# schematicsch.net
KiCad netlist of a schematic drawn in EAGLE
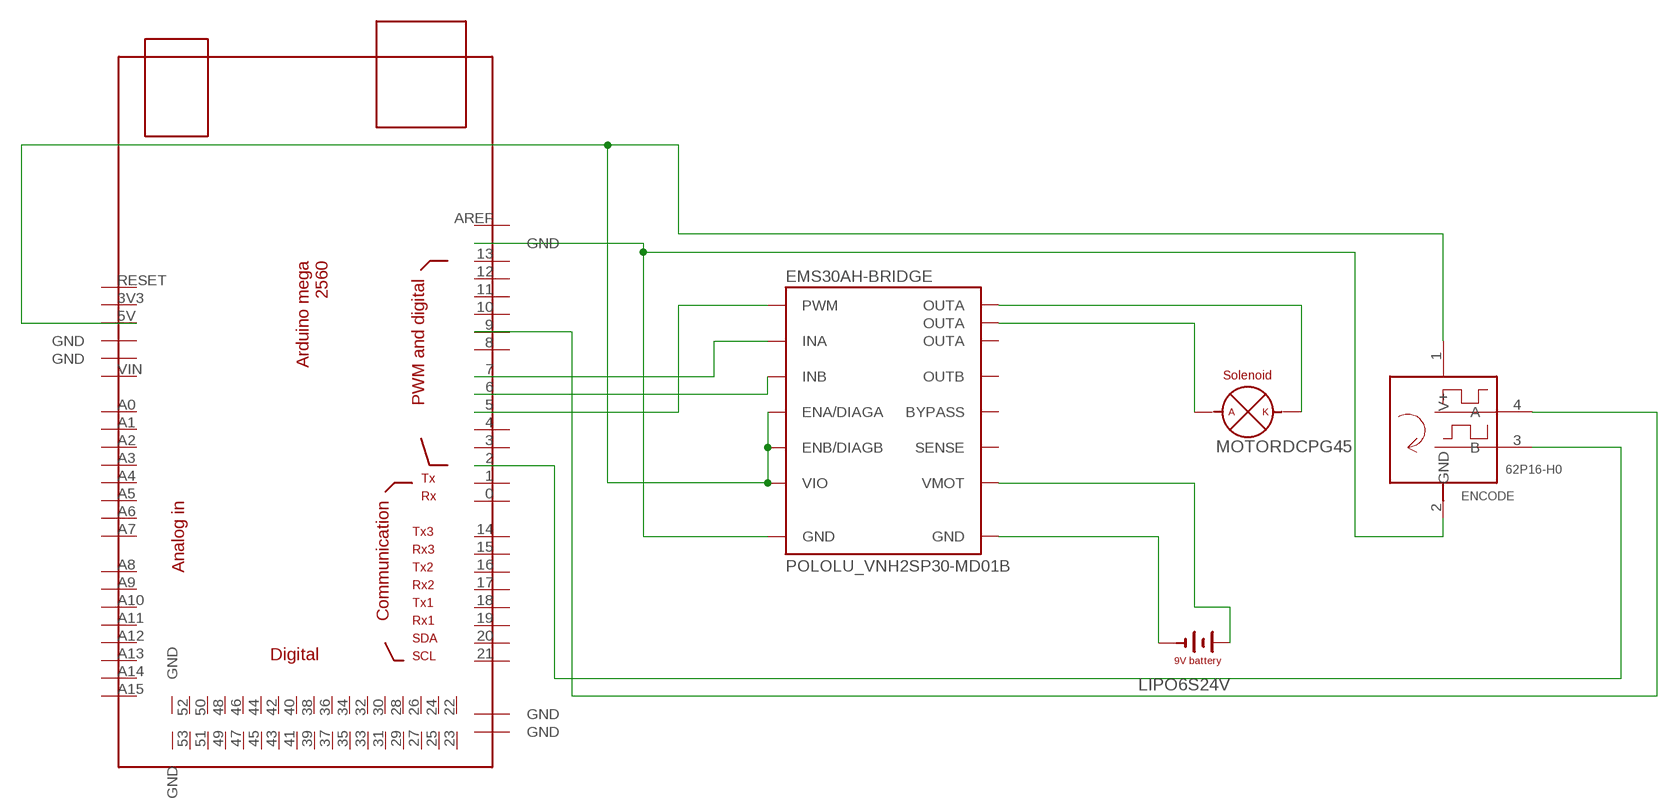
[diagram p0: schematic, sheet 1]

(export (version "E")
  (design (tool "Eeschema 10.0.6"))
  (components
    (comp (ref "EMS30AH-BRIDGE")
      (value "POLOLU_VNH2SP30-MD01B")
      (footprint "eagle-import:POLOLU_MD01B_P")
      (libsource (lib "eagle-import") (part "POLOLU_VNH2SP30-MD01B"))
    )
    (comp (ref "ENCODE")
      (value "62P16-H0")
      (footprint "eagle-import:62P")
      (libsource (lib "eagle-import") (part "62P016-H"))
    )
    (comp (ref "LIPO6S24V")
      (value "-9VBAT")
      (footprint "eagle-import:BAT")
      (libsource (lib "eagle-import") (part "-9VBAT"))
    )
    (comp (ref "MOTORDCPG45")
      (value "-MOTOR")
      (footprint "eagle-import:CON2")
      (libsource (lib "eagle-import") (part "-MOTOR"))
    )
    (comp (ref "U$1")
      (value "MEGA_DEVICE")
      (footprint "eagle-import:MEGAOUTLINE")
      (libsource (lib "eagle-import") (part "MEGA_DEVICE"))
    )
  )
  (nets
    (net (code "1") (name "/BYPASS") (class "Default")
      (node (ref "EMS30AH-BRIDGE") (pin "BYP") (pinfunction "BYPASS_BYP") (pintype "power_in"))
    )
    (net (code "2") (name "Net-(EMS30AH-BRIDGE-ENA{slash}DIAGA)") (class "Default")
      (node (ref "EMS30AH-BRIDGE") (pin "ENA") (pinfunction "ENA/DIAGA_ENA") (pintype "open_collector"))
      (node (ref "EMS30AH-BRIDGE") (pin "ENB") (pinfunction "ENB/DIAGB_ENB") (pintype "open_collector"))
      (node (ref "EMS30AH-BRIDGE") (pin "VIO") (pinfunction "VIO_VIO") (pintype "power_in"))
      (node (ref "ENCODE") (pin "1") (pinfunction "V+_1") (pintype "power_in"))
      (node (ref "U$1") (pin "5V") (pinfunction "5V_5V") (pintype "bidirectional"))
    )
    (net (code "3") (name "Net-(EMS30AH-BRIDGE-GND-PadGND2)") (class "Default")
      (node (ref "EMS30AH-BRIDGE") (pin "GND2") (pinfunction "GND_GND2") (pintype "power_in"))
      (node (ref "LIPO6S24V") (pin "-") (pinfunction "-_-") (pintype "passive"))
    )
    (net (code "4") (name "Net-(EMS30AH-BRIDGE-PadINA)") (class "Default")
      (node (ref "EMS30AH-BRIDGE") (pin "INA") (pinfunction "INA_INA") (pintype "input"))
      (node (ref "U$1") (pin "7") (pinfunction "7_7") (pintype "bidirectional"))
    )
    (net (code "5") (name "Net-(EMS30AH-BRIDGE-PadINB)") (class "Default")
      (node (ref "EMS30AH-BRIDGE") (pin "INB") (pinfunction "INB_INB") (pintype "input"))
      (node (ref "U$1") (pin "6") (pinfunction "6_6") (pintype "bidirectional"))
    )
    (net (code "6") (name "Net-(EMS30AH-BRIDGE-PadPWM)") (class "Default")
      (node (ref "EMS30AH-BRIDGE") (pin "PWM") (pinfunction "PWM_PWM") (pintype "input"))
      (node (ref "U$1") (pin "5") (pinfunction "5_5") (pintype "bidirectional"))
    )
    (net (code "7") (name "Net-(EMS30AH-BRIDGE-PadVMOT)") (class "Default")
      (node (ref "EMS30AH-BRIDGE") (pin "VMOT") (pinfunction "VMOT_VMOT") (pintype "power_in"))
      (node (ref "LIPO6S24V") (pin "+") (pinfunction "+_+") (pintype "passive"))
    )
    (net (code "8") (name "Net-(ENCODE-A)") (class "Default")
      (node (ref "ENCODE") (pin "4") (pinfunction "A_4") (pintype "bidirectional"))
      (node (ref "U$1") (pin "9") (pinfunction "9_9") (pintype "bidirectional"))
    )
    (net (code "9") (name "Net-(ENCODE-B)") (class "Default")
      (node (ref "ENCODE") (pin "3") (pinfunction "B_3") (pintype "bidirectional"))
      (node (ref "U$1") (pin "2") (pinfunction "2_2") (pintype "bidirectional"))
    )
    (net (code "10") (name "Net-(ENCODE-GND)") (class "Default")
      (node (ref "EMS30AH-BRIDGE") (pin "GND1") (pinfunction "GND_GND1") (pintype "power_in"))
      (node (ref "ENCODE") (pin "2") (pinfunction "GND_2") (pintype "power_in"))
      (node (ref "U$1") (pin "GND@1") (pinfunction "GND_GND@1") (pintype "bidirectional"))
    )
    (net (code "11") (name "Net-(MOTORDCPG45-+)") (class "Default")
      (node (ref "EMS30AH-BRIDGE") (pin "OUTA2") (pinfunction "OUTA_OUTA2") (pintype "output"))
      (node (ref "MOTORDCPG45") (pin "P$1") (pinfunction "+_P$1") (pintype "passive"))
    )
    (net (code "12") (name "Net-(MOTORDCPG45--)") (class "Default")
      (node (ref "EMS30AH-BRIDGE") (pin "OUTA3") (pinfunction "OUTA_OUTA3") (pintype "output"))
      (node (ref "MOTORDCPG45") (pin "P$2") (pinfunction "-_P$2") (pintype "passive"))
    )
    (net (code "13") (name "unconnected-(EMS30AH-BRIDGE-OUTA-PadOUTA1)") (class "Default")
      (node (ref "EMS30AH-BRIDGE") (pin "OUTA1") (pinfunction "OUTA_OUTA1") (pintype "output"))
    )
    (net (code "14") (name "unconnected-(EMS30AH-BRIDGE-PadOUTB)") (class "Default")
      (node (ref "EMS30AH-BRIDGE") (pin "OUTB") (pinfunction "OUTB_OUTB") (pintype "output"))
    )
    (net (code "15") (name "unconnected-(EMS30AH-BRIDGE-PadSENSE)") (class "Default")
      (node (ref "EMS30AH-BRIDGE") (pin "SENSE") (pinfunction "SENSE_SENSE") (pintype "passive"))
    )
    (net (code "16") (name "unconnected-(U$1-GND-PadGND@2)") (class "Default")
      (node (ref "U$1") (pin "GND@2") (pinfunction "GND_GND@2") (pintype "bidirectional"))
    )
    (net (code "17") (name "unconnected-(U$1-GND-PadGND@3)") (class "Default")
      (node (ref "U$1") (pin "GND@3") (pinfunction "GND_GND@3") (pintype "bidirectional"))
    )
    (net (code "18") (name "unconnected-(U$1-GND-PadGND@4)") (class "Default")
      (node (ref "U$1") (pin "GND@4") (pinfunction "GND_GND@4") (pintype "bidirectional"))
    )
    (net (code "19") (name "unconnected-(U$1-GND-PadGND@5)") (class "Default")
      (node (ref "U$1") (pin "GND@5") (pinfunction "GND_GND@5") (pintype "bidirectional"))
    )
    (net (code "20") (name "unconnected-(U$1-GND-PadGND@6)") (class "Default")
      (node (ref "U$1") (pin "GND@6") (pinfunction "GND_GND@6") (pintype "bidirectional"))
    )
    (net (code "21") (name "unconnected-(U$1-GND-PadGND@7)") (class "Default")
      (node (ref "U$1") (pin "GND@7") (pinfunction "GND_GND@7") (pintype "bidirectional"))
    )
    (net (code "22") (name "unconnected-(U$1-Pad0)") (class "Default")
      (node (ref "U$1") (pin "0") (pinfunction "0_0") (pintype "bidirectional"))
    )
    (net (code "23") (name "unconnected-(U$1-Pad1)") (class "Default")
      (node (ref "U$1") (pin "1") (pinfunction "1_1") (pintype "bidirectional"))
    )
    (net (code "24") (name "unconnected-(U$1-Pad3)") (class "Default")
      (node (ref "U$1") (pin "3") (pinfunction "3_3") (pintype "bidirectional"))
    )
    (net (code "25") (name "unconnected-(U$1-Pad3V3)") (class "Default")
      (node (ref "U$1") (pin "3V3") (pinfunction "3V3_3V3") (pintype "bidirectional"))
    )
    (net (code "26") (name "unconnected-(U$1-Pad4)") (class "Default")
      (node (ref "U$1") (pin "4") (pinfunction "4_4") (pintype "bidirectional"))
    )
    (net (code "27") (name "unconnected-(U$1-Pad8)") (class "Default")
      (node (ref "U$1") (pin "8") (pinfunction "8_8") (pintype "bidirectional"))
    )
    (net (code "28") (name "unconnected-(U$1-Pad10)") (class "Default")
      (node (ref "U$1") (pin "10") (pinfunction "10_10") (pintype "bidirectional"))
    )
    (net (code "29") (name "unconnected-(U$1-Pad11)") (class "Default")
      (node (ref "U$1") (pin "11") (pinfunction "11_11") (pintype "bidirectional"))
    )
    (net (code "30") (name "unconnected-(U$1-Pad12)") (class "Default")
      (node (ref "U$1") (pin "12") (pinfunction "12_12") (pintype "bidirectional"))
    )
    (net (code "31") (name "unconnected-(U$1-Pad13)") (class "Default")
      (node (ref "U$1") (pin "13") (pinfunction "13_13") (pintype "bidirectional"))
    )
    (net (code "32") (name "unconnected-(U$1-Pad14)") (class "Default")
      (node (ref "U$1") (pin "14") (pinfunction "14_14") (pintype "bidirectional"))
    )
    (net (code "33") (name "unconnected-(U$1-Pad15)") (class "Default")
      (node (ref "U$1") (pin "15") (pinfunction "15_15") (pintype "bidirectional"))
    )
    (net (code "34") (name "unconnected-(U$1-Pad16)") (class "Default")
      (node (ref "U$1") (pin "16") (pinfunction "16_16") (pintype "bidirectional"))
    )
    (net (code "35") (name "unconnected-(U$1-Pad17)") (class "Default")
      (node (ref "U$1") (pin "17") (pinfunction "17_17") (pintype "bidirectional"))
    )
    (net (code "36") (name "unconnected-(U$1-Pad18)") (class "Default")
      (node (ref "U$1") (pin "18") (pinfunction "18_18") (pintype "bidirectional"))
    )
    (net (code "37") (name "unconnected-(U$1-Pad19)") (class "Default")
      (node (ref "U$1") (pin "19") (pinfunction "19_19") (pintype "bidirectional"))
    )
    (net (code "38") (name "unconnected-(U$1-Pad20)") (class "Default")
      (node (ref "U$1") (pin "20") (pinfunction "20_20") (pintype "bidirectional"))
    )
    (net (code "39") (name "unconnected-(U$1-Pad21)") (class "Default")
      (node (ref "U$1") (pin "21") (pinfunction "21_21") (pintype "bidirectional"))
    )
    (net (code "40") (name "unconnected-(U$1-Pad22)") (class "Default")
      (node (ref "U$1") (pin "22") (pinfunction "22_22") (pintype "bidirectional"))
    )
    (net (code "41") (name "unconnected-(U$1-Pad23)") (class "Default")
      (node (ref "U$1") (pin "23") (pinfunction "23_23") (pintype "bidirectional"))
    )
    (net (code "42") (name "unconnected-(U$1-Pad24)") (class "Default")
      (node (ref "U$1") (pin "24") (pinfunction "24_24") (pintype "bidirectional"))
    )
    (net (code "43") (name "unconnected-(U$1-Pad25)") (class "Default")
      (node (ref "U$1") (pin "25") (pinfunction "25_25") (pintype "bidirectional"))
    )
    (net (code "44") (name "unconnected-(U$1-Pad26)") (class "Default")
      (node (ref "U$1") (pin "26") (pinfunction "26_26") (pintype "bidirectional"))
    )
    (net (code "45") (name "unconnected-(U$1-Pad27)") (class "Default")
      (node (ref "U$1") (pin "27") (pinfunction "27_27") (pintype "bidirectional"))
    )
    (net (code "46") (name "unconnected-(U$1-Pad28)") (class "Default")
      (node (ref "U$1") (pin "28") (pinfunction "28_28") (pintype "bidirectional"))
    )
    (net (code "47") (name "unconnected-(U$1-Pad29)") (class "Default")
      (node (ref "U$1") (pin "29") (pinfunction "29_29") (pintype "bidirectional"))
    )
    (net (code "48") (name "unconnected-(U$1-Pad30)") (class "Default")
      (node (ref "U$1") (pin "30") (pinfunction "30_30") (pintype "bidirectional"))
    )
    (net (code "49") (name "unconnected-(U$1-Pad31)") (class "Default")
      (node (ref "U$1") (pin "31") (pinfunction "31_31") (pintype "bidirectional"))
    )
    (net (code "50") (name "unconnected-(U$1-Pad32)") (class "Default")
      (node (ref "U$1") (pin "32") (pinfunction "32_32") (pintype "bidirectional"))
    )
    (net (code "51") (name "unconnected-(U$1-Pad33)") (class "Default")
      (node (ref "U$1") (pin "33") (pinfunction "33_33") (pintype "bidirectional"))
    )
    (net (code "52") (name "unconnected-(U$1-Pad34)") (class "Default")
      (node (ref "U$1") (pin "34") (pinfunction "34_34") (pintype "bidirectional"))
    )
    (net (code "53") (name "unconnected-(U$1-Pad35)") (class "Default")
      (node (ref "U$1") (pin "35") (pinfunction "35_35") (pintype "bidirectional"))
    )
    (net (code "54") (name "unconnected-(U$1-Pad36)") (class "Default")
      (node (ref "U$1") (pin "36") (pinfunction "36_36") (pintype "bidirectional"))
    )
    (net (code "55") (name "unconnected-(U$1-Pad37)") (class "Default")
      (node (ref "U$1") (pin "37") (pinfunction "37_37") (pintype "bidirectional"))
    )
    (net (code "56") (name "unconnected-(U$1-Pad38)") (class "Default")
      (node (ref "U$1") (pin "38") (pinfunction "38_38") (pintype "bidirectional"))
    )
    (net (code "57") (name "unconnected-(U$1-Pad39)") (class "Default")
      (node (ref "U$1") (pin "39") (pinfunction "39_39") (pintype "bidirectional"))
    )
    (net (code "58") (name "unconnected-(U$1-Pad40)") (class "Default")
      (node (ref "U$1") (pin "40") (pinfunction "40_40") (pintype "bidirectional"))
    )
    (net (code "59") (name "unconnected-(U$1-Pad41)") (class "Default")
      (node (ref "U$1") (pin "41") (pinfunction "41_41") (pintype "bidirectional"))
    )
    (net (code "60") (name "unconnected-(U$1-Pad42)") (class "Default")
      (node (ref "U$1") (pin "42") (pinfunction "42_42") (pintype "bidirectional"))
    )
    (net (code "61") (name "unconnected-(U$1-Pad43)") (class "Default")
      (node (ref "U$1") (pin "43") (pinfunction "43_43") (pintype "bidirectional"))
    )
    (net (code "62") (name "unconnected-(U$1-Pad44)") (class "Default")
      (node (ref "U$1") (pin "44") (pinfunction "44_44") (pintype "bidirectional"))
    )
    (net (code "63") (name "unconnected-(U$1-Pad45)") (class "Default")
      (node (ref "U$1") (pin "45") (pinfunction "45_45") (pintype "bidirectional"))
    )
    (net (code "64") (name "unconnected-(U$1-Pad46)") (class "Default")
      (node (ref "U$1") (pin "46") (pinfunction "46_46") (pintype "bidirectional"))
    )
    (net (code "65") (name "unconnected-(U$1-Pad47)") (class "Default")
      (node (ref "U$1") (pin "47") (pinfunction "47_47") (pintype "bidirectional"))
    )
    (net (code "66") (name "unconnected-(U$1-Pad48)") (class "Default")
      (node (ref "U$1") (pin "48") (pinfunction "48_48") (pintype "bidirectional"))
    )
    (net (code "67") (name "unconnected-(U$1-Pad49)") (class "Default")
      (node (ref "U$1") (pin "49") (pinfunction "49_49") (pintype "bidirectional"))
    )
    (net (code "68") (name "unconnected-(U$1-Pad50)") (class "Default")
      (node (ref "U$1") (pin "50") (pinfunction "50_50") (pintype "bidirectional"))
    )
    (net (code "69") (name "unconnected-(U$1-Pad51)") (class "Default")
      (node (ref "U$1") (pin "51") (pinfunction "51_51") (pintype "bidirectional"))
    )
    (net (code "70") (name "unconnected-(U$1-Pad52)") (class "Default")
      (node (ref "U$1") (pin "52") (pinfunction "52_52") (pintype "bidirectional"))
    )
    (net (code "71") (name "unconnected-(U$1-Pad53)") (class "Default")
      (node (ref "U$1") (pin "53") (pinfunction "53_53") (pintype "bidirectional"))
    )
    (net (code "72") (name "unconnected-(U$1-PadA0)") (class "Default")
      (node (ref "U$1") (pin "A0") (pinfunction "A0_A0") (pintype "bidirectional"))
    )
    (net (code "73") (name "unconnected-(U$1-PadA1)") (class "Default")
      (node (ref "U$1") (pin "A1") (pinfunction "A1_A1") (pintype "bidirectional"))
    )
    (net (code "74") (name "unconnected-(U$1-PadA2)") (class "Default")
      (node (ref "U$1") (pin "A2") (pinfunction "A2_A2") (pintype "bidirectional"))
    )
    (net (code "75") (name "unconnected-(U$1-PadA3)") (class "Default")
      (node (ref "U$1") (pin "A3") (pinfunction "A3_A3") (pintype "bidirectional"))
    )
    (net (code "76") (name "unconnected-(U$1-PadA4)") (class "Default")
      (node (ref "U$1") (pin "A4") (pinfunction "A4_A4") (pintype "bidirectional"))
    )
    (net (code "77") (name "unconnected-(U$1-PadA5)") (class "Default")
      (node (ref "U$1") (pin "A5") (pinfunction "A5_A5") (pintype "bidirectional"))
    )
    (net (code "78") (name "unconnected-(U$1-PadA6)") (class "Default")
      (node (ref "U$1") (pin "A6") (pinfunction "A6_A6") (pintype "bidirectional"))
    )
    (net (code "79") (name "unconnected-(U$1-PadA7)") (class "Default")
      (node (ref "U$1") (pin "A7") (pinfunction "A7_A7") (pintype "bidirectional"))
    )
    (net (code "80") (name "unconnected-(U$1-PadA8)") (class "Default")
      (node (ref "U$1") (pin "A8") (pinfunction "A8_A8") (pintype "bidirectional"))
    )
    (net (code "81") (name "unconnected-(U$1-PadA9)") (class "Default")
      (node (ref "U$1") (pin "A9") (pinfunction "A9_A9") (pintype "bidirectional"))
    )
    (net (code "82") (name "unconnected-(U$1-PadA10)") (class "Default")
      (node (ref "U$1") (pin "A10") (pinfunction "A10_A10") (pintype "bidirectional"))
    )
    (net (code "83") (name "unconnected-(U$1-PadA11)") (class "Default")
      (node (ref "U$1") (pin "A11") (pinfunction "A11_A11") (pintype "bidirectional"))
    )
    (net (code "84") (name "unconnected-(U$1-PadA12)") (class "Default")
      (node (ref "U$1") (pin "A12") (pinfunction "A12_A12") (pintype "bidirectional"))
    )
    (net (code "85") (name "unconnected-(U$1-PadA13)") (class "Default")
      (node (ref "U$1") (pin "A13") (pinfunction "A13_A13") (pintype "bidirectional"))
    )
    (net (code "86") (name "unconnected-(U$1-PadA14)") (class "Default")
      (node (ref "U$1") (pin "A14") (pinfunction "A14_A14") (pintype "bidirectional"))
    )
    (net (code "87") (name "unconnected-(U$1-PadA15)") (class "Default")
      (node (ref "U$1") (pin "A15") (pinfunction "A15_A15") (pintype "bidirectional"))
    )
    (net (code "88") (name "unconnected-(U$1-PadAREF)") (class "Default")
      (node (ref "U$1") (pin "AREF") (pinfunction "AREF_AREF") (pintype "bidirectional"))
    )
    (net (code "89") (name "unconnected-(U$1-PadRESET)") (class "Default")
      (node (ref "U$1") (pin "RESET") (pinfunction "RESET_RESET") (pintype "bidirectional"))
    )
    (net (code "90") (name "unconnected-(U$1-PadVIN)") (class "Default")
      (node (ref "U$1") (pin "VIN") (pinfunction "VIN_VIN") (pintype "bidirectional"))
    )
  )
)
